# qPCR_pcb_breakout_ADS1219IPWR.net
KiCad netlist of a schematic drawn in EAGLE
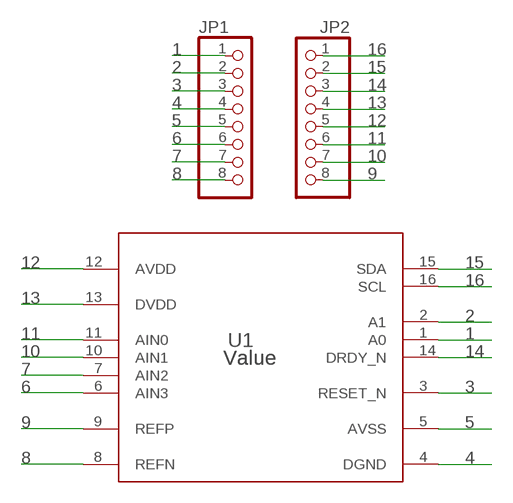
[diagram p0: schematic, sheet 1]

(export (version "E")
  (design (tool "Eeschema 10.0.6"))
  (components
    (comp (ref "JP1")
      (value "PINHD-1X8")
      (footprint "eagle-import:1X08")
      (libsource (lib "eagle-import") (part "PINHD-1X8"))
    )
    (comp (ref "JP2")
      (value "PINHD-1X8")
      (footprint "eagle-import:1X08")
      (libsource (lib "eagle-import") (part "PINHD-1X8"))
    )
    (comp (ref "U1")
      (value "Value")
      (footprint "eagle-import:PW0016A_N")
      (fields (field (name "MANUFACTURER") "Texas Instruments") (field (name "PARTNUMBER") "ADS1219IPWR"))
      (libsource (lib "eagle-import") (part "ADS1219IPW"))
    )
  )
  (nets
    (net (code "1") (name "/1") (class "Default")
      (node (ref "JP1") (pin "1") (pinfunction "1_1") (pintype "passive"))
      (node (ref "U1") (pin "1") (pinfunction "A0_1") (pintype "input"))
    )
    (net (code "2") (name "/2") (class "Default")
      (node (ref "JP1") (pin "2") (pinfunction "2_2") (pintype "passive"))
      (node (ref "U1") (pin "2") (pinfunction "A1_2") (pintype "input"))
    )
    (net (code "3") (name "/3") (class "Default")
      (node (ref "JP1") (pin "3") (pinfunction "3_3") (pintype "passive"))
      (node (ref "U1") (pin "3") (pinfunction "RESET_N_3") (pintype "input"))
    )
    (net (code "4") (name "/4") (class "Default")
      (node (ref "JP1") (pin "4") (pinfunction "4_4") (pintype "passive"))
      (node (ref "U1") (pin "4") (pinfunction "DGND_4") (pintype "power_in"))
    )
    (net (code "5") (name "/5") (class "Default")
      (node (ref "JP1") (pin "5") (pinfunction "5_5") (pintype "passive"))
      (node (ref "U1") (pin "5") (pinfunction "AVSS_5") (pintype "power_in"))
    )
    (net (code "6") (name "/6") (class "Default")
      (node (ref "JP1") (pin "6") (pinfunction "6_6") (pintype "passive"))
      (node (ref "U1") (pin "6") (pinfunction "AIN3_6") (pintype "input"))
    )
    (net (code "7") (name "/7") (class "Default")
      (node (ref "JP1") (pin "7") (pinfunction "7_7") (pintype "passive"))
      (node (ref "U1") (pin "7") (pinfunction "AIN2_7") (pintype "input"))
    )
    (net (code "8") (name "/8") (class "Default")
      (node (ref "JP1") (pin "8") (pinfunction "8_8") (pintype "passive"))
      (node (ref "U1") (pin "8") (pinfunction "REFN_8") (pintype "input"))
    )
    (net (code "9") (name "/9") (class "Default")
      (node (ref "JP2") (pin "8") (pinfunction "8_8") (pintype "passive"))
      (node (ref "U1") (pin "9") (pinfunction "REFP_9") (pintype "input"))
    )
    (net (code "10") (name "/10") (class "Default")
      (node (ref "JP2") (pin "7") (pinfunction "7_7") (pintype "passive"))
      (node (ref "U1") (pin "10") (pinfunction "AIN1_10") (pintype "input"))
    )
    (net (code "11") (name "/11") (class "Default")
      (node (ref "JP2") (pin "6") (pinfunction "6_6") (pintype "passive"))
      (node (ref "U1") (pin "11") (pinfunction "AIN0_11") (pintype "input"))
    )
    (net (code "12") (name "/12") (class "Default")
      (node (ref "JP2") (pin "5") (pinfunction "5_5") (pintype "passive"))
      (node (ref "U1") (pin "12") (pinfunction "AVDD_12") (pintype "power_in"))
    )
    (net (code "13") (name "/13") (class "Default")
      (node (ref "JP2") (pin "4") (pinfunction "4_4") (pintype "passive"))
      (node (ref "U1") (pin "13") (pinfunction "DVDD_13") (pintype "power_in"))
    )
    (net (code "14") (name "/14") (class "Default")
      (node (ref "JP2") (pin "3") (pinfunction "3_3") (pintype "passive"))
      (node (ref "U1") (pin "14") (pinfunction "DRDY_N_14") (pintype "output"))
    )
    (net (code "15") (name "/15") (class "Default")
      (node (ref "JP2") (pin "2") (pinfunction "2_2") (pintype "passive"))
      (node (ref "U1") (pin "15") (pinfunction "SDA_15") (pintype "bidirectional"))
    )
    (net (code "16") (name "/16") (class "Default")
      (node (ref "JP2") (pin "1") (pinfunction "1_1") (pintype "passive"))
      (node (ref "U1") (pin "16") (pinfunction "SCL_16") (pintype "input"))
    )
  )
)
